# Interfaces.net
KiCad netlist of a schematic drawn in Altium Designer
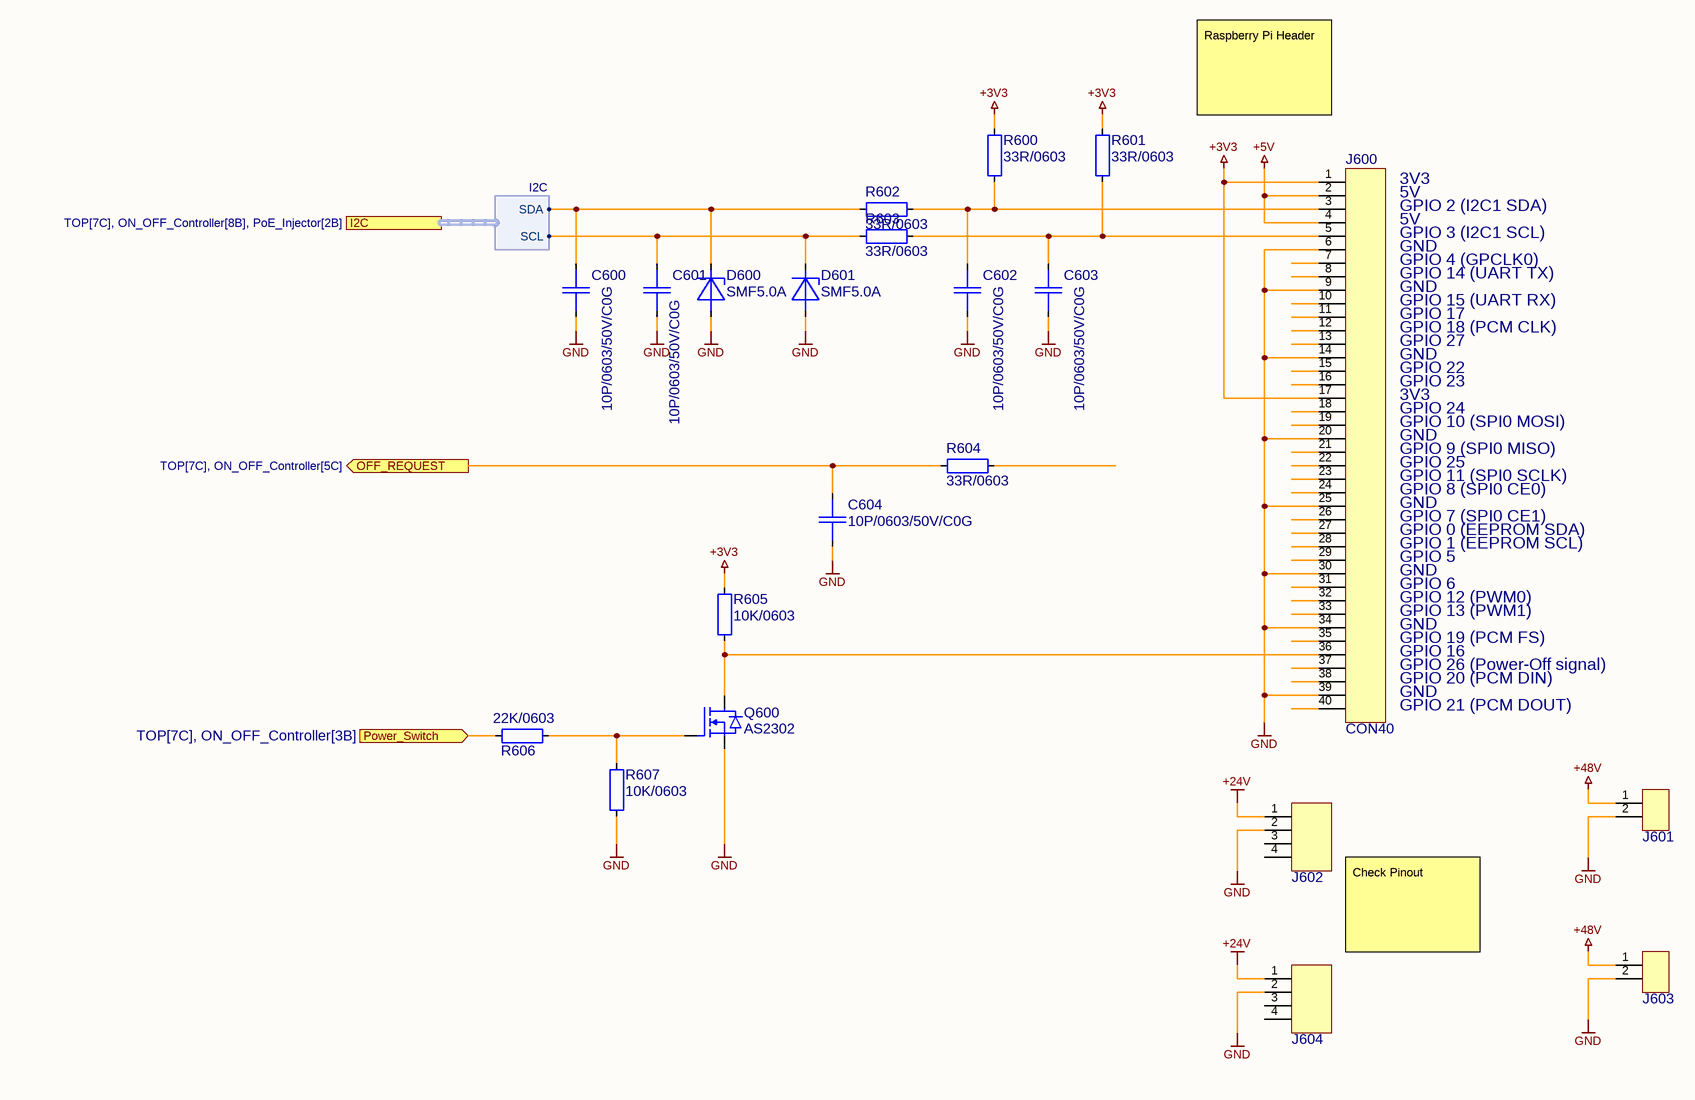
[diagram p0: Interfaces.SchDoc]

(export (version "E")
  (design (tool "Eeschema 10.0.6"))
  (components
    (comp (ref "C600")
      (value "10P/0603/50V/C0G")
      (footprint "CAP0603_C0G")
      (description "CAP SM 0603 10pF 50V C0G")
      (fields (field (name "MANUFACTURER") "GENERIC"))
      (libsource (lib "daniw_altium_lib") (part "C"))
    )
    (comp (ref "C601")
      (value "10P/0603/50V/C0G")
      (footprint "CAP0603_C0G")
      (description "CAP SM 0603 10pF 50V C0G")
      (fields (field (name "MANUFACTURER") "GENERIC"))
      (libsource (lib "daniw_altium_lib") (part "C"))
    )
    (comp (ref "C602")
      (value "10P/0603/50V/C0G")
      (footprint "CAP0603_C0G")
      (description "CAP SM 0603 10pF 50V C0G")
      (fields (field (name "MANUFACTURER") "GENERIC"))
      (libsource (lib "daniw_altium_lib") (part "C"))
    )
    (comp (ref "C603")
      (value "10P/0603/50V/C0G")
      (footprint "CAP0603_C0G")
      (description "CAP SM 0603 10pF 50V C0G")
      (fields (field (name "MANUFACTURER") "GENERIC"))
      (libsource (lib "daniw_altium_lib") (part "C"))
    )
    (comp (ref "C604")
      (value "10P/0603/50V/C0G")
      (footprint "CAP0603_C0G")
      (description "CAP SM 0603 10pF 50V C0G")
      (fields (field (name "MANUFACTURER") "GENERIC"))
      (libsource (lib "daniw_altium_lib") (part "C"))
    )
    (comp (ref "D600")
      (value "SMF5.0A")
      (footprint "SOD3720X110")
      (description "TVS DIODE 5VWM 9.2VC SOD123F")
      (fields (field (name "MANUFACTURER") "Littelfuse Inc."))
      (libsource (lib "daniw_altium_lib") (part "D_Zener"))
    )
    (comp (ref "D601")
      (value "SMF5.0A")
      (footprint "SOD3720X110")
      (description "TVS DIODE 5VWM 9.2VC SOD123F")
      (fields (field (name "MANUFACTURER") "Littelfuse Inc."))
      (libsource (lib "daniw_altium_lib") (part "D_Zener"))
    )
    (comp (ref "J600")
      (value "CON40")
      (footprint "HEAD_254_2X20")
      (description "Header 100 mil")
      (fields (field (name "PART NUMBER") "Header_2x20") (field (name "MANUFACTURER") "GENERIC"))
      (libsource (lib "daniw_altium_lib") (part "CON40"))
    )
    (comp (ref "J601")
      (value "430450212")
      (footprint "430450212")
      (fields (field (name "PART NUMBER") "Microfit_3.0_1x2_VERT_THT"))
      (libsource (lib "daniw_altium_lib") (part "CON2"))
    )
    (comp (ref "J602")
      (value "430450412")
      (footprint "430450412")
      (fields (field (name "PART NUMBER") "Microfit_3.0_2x2_VERT_THT"))
      (libsource (lib "daniw_altium_lib") (part "CON4"))
    )
    (comp (ref "J603")
      (value "430450212")
      (footprint "430450212")
      (fields (field (name "PART NUMBER") "Microfit_3.0_1x2_VERT_THT"))
      (libsource (lib "daniw_altium_lib") (part "CON2"))
    )
    (comp (ref "J604")
      (value "430450412")
      (footprint "430450412")
      (fields (field (name "PART NUMBER") "Microfit_3.0_2x2_VERT_THT"))
      (libsource (lib "daniw_altium_lib") (part "CON4"))
    )
    (comp (ref "Q600")
      (value "AS2302")
      (footprint "SOT2395P280X125-3-SE")
      (description "N-Channel 20V(D-S) MOSFET")
      (fields (field (name "MANUFACTURER") "GENERIC"))
      (libsource (lib "daniw_altium_lib") (part "MOSFET N_SOT23"))
    )
    (comp (ref "R600")
      (value "33R/0603")
      (footprint "R0603-0.40-WW")
      (description "RES SM 0603 33R")
      (fields (field (name "MANUFACTURER") "GENERIC"))
      (libsource (lib "daniw_altium_lib") (part "R"))
    )
    (comp (ref "R601")
      (value "33R/0603")
      (footprint "R0603-0.40-WW")
      (description "RES SM 0603 33R")
      (fields (field (name "MANUFACTURER") "GENERIC"))
      (libsource (lib "daniw_altium_lib") (part "R"))
    )
    (comp (ref "R602")
      (value "33R/0603")
      (footprint "R0603-0.40-WW")
      (description "RES SM 0603 33R")
      (fields (field (name "MANUFACTURER") "GENERIC"))
      (libsource (lib "daniw_altium_lib") (part "R"))
    )
    (comp (ref "R603")
      (value "33R/0603")
      (footprint "R0603-0.40-WW")
      (description "RES SM 0603 33R")
      (fields (field (name "MANUFACTURER") "GENERIC"))
      (libsource (lib "daniw_altium_lib") (part "R"))
    )
    (comp (ref "R604")
      (value "33R/0603")
      (footprint "R0603-0.40-WW")
      (description "RES SM 0603 33R")
      (fields (field (name "MANUFACTURER") "GENERIC"))
      (libsource (lib "daniw_altium_lib") (part "R"))
    )
    (comp (ref "R605")
      (value "10K/0603")
      (footprint "R0603-0.40-WW")
      (description "RES SM 0603 10K")
      (fields (field (name "MANUFACTURER") "GENERIC"))
      (libsource (lib "daniw_altium_lib") (part "R"))
    )
    (comp (ref "R606")
      (value "22K/0603")
      (footprint "R0603-0.40-WW")
      (description "RES SM 0603 22K")
      (fields (field (name "MANUFACTURER") "GENERIC"))
      (libsource (lib "daniw_altium_lib") (part "R"))
    )
    (comp (ref "R607")
      (value "10K/0603")
      (footprint "R0603-0.40-WW")
      (description "RES SM 0603 10K")
      (fields (field (name "MANUFACTURER") "GENERIC"))
      (libsource (lib "daniw_altium_lib") (part "R"))
    )
  )
  (nets
    (net (code "2") (name "+3V3") (class "Default")
      (node (ref "J600") (pin "1") (pintype "passive"))
      (node (ref "J600") (pin "17") (pintype "passive"))
      (node (ref "R600") (pin "2") (pinfunction "2_2") (pintype "passive"))
      (node (ref "R601") (pin "2") (pinfunction "2_2") (pintype "passive"))
      (node (ref "R605") (pin "1") (pinfunction "1_1") (pintype "passive"))
    )
    (net (code "3") (name "+5V") (class "Default")
      (node (ref "J600") (pin "2") (pintype "passive"))
      (node (ref "J600") (pin "4") (pintype "passive"))
    )
    (net (code "4") (name "+24V") (class "Default")
      (node (ref "J602") (pin "1") (pintype "passive"))
      (node (ref "J604") (pin "1") (pintype "passive"))
    )
    (net (code "5") (name "+48V") (class "Default")
      (node (ref "J601") (pin "1") (pintype "passive"))
      (node (ref "J603") (pin "1") (pintype "passive"))
    )
    (net (code "6") (name "/OFF_REQUEST") (class "Default")
      (node (ref "C604") (pin "1") (pinfunction "1_1") (pintype "passive"))
      (node (ref "R604") (pin "1") (pinfunction "1_1") (pintype "passive"))
    )
    (net (code "7") (name "/Power_Switch") (class "Default")
      (node (ref "R606") (pin "1") (pinfunction "1_1") (pintype "passive"))
    )
    (net (code "9") (name "GND") (class "Default")
      (node (ref "C600") (pin "2") (pinfunction "2_2") (pintype "passive"))
      (node (ref "C601") (pin "2") (pinfunction "2_2") (pintype "passive"))
      (node (ref "C602") (pin "2") (pinfunction "2_2") (pintype "passive"))
      (node (ref "C603") (pin "2") (pinfunction "2_2") (pintype "passive"))
      (node (ref "C604") (pin "2") (pinfunction "2_2") (pintype "passive"))
      (node (ref "D600") (pin "2") (pinfunction "2_2") (pintype "passive"))
      (node (ref "D601") (pin "2") (pinfunction "2_2") (pintype "passive"))
      (node (ref "J600") (pin "14") (pintype "passive"))
      (node (ref "J600") (pin "20") (pintype "passive"))
      (node (ref "J600") (pin "25") (pintype "passive"))
      (node (ref "J600") (pin "30") (pintype "passive"))
      (node (ref "J600") (pin "34") (pintype "passive"))
      (node (ref "J600") (pin "39") (pintype "passive"))
      (node (ref "J600") (pin "6") (pintype "passive"))
      (node (ref "J600") (pin "9") (pintype "passive"))
      (node (ref "J601") (pin "2") (pintype "passive"))
      (node (ref "J602") (pin "2") (pintype "passive"))
      (node (ref "J603") (pin "2") (pintype "passive"))
      (node (ref "J604") (pin "2") (pintype "passive"))
      (node (ref "Q600") (pin "2") (pinfunction "SOURCE_2") (pintype "passive"))
      (node (ref "R607") (pin "2") (pinfunction "2_2") (pintype "passive"))
    )
    (net (code "10") (name "Net-(C600-Pad1)") (class "Default")
      (node (ref "C600") (pin "1") (pinfunction "1_1") (pintype "passive"))
      (node (ref "D600") (pin "1") (pinfunction "1_1") (pintype "passive"))
      (node (ref "R602") (pin "1") (pinfunction "1_1") (pintype "passive"))
    )
    (net (code "11") (name "Net-(C601-Pad1)") (class "Default")
      (node (ref "C601") (pin "1") (pinfunction "1_1") (pintype "passive"))
      (node (ref "D601") (pin "1") (pinfunction "1_1") (pintype "passive"))
      (node (ref "R603") (pin "1") (pinfunction "1_1") (pintype "passive"))
    )
    (net (code "12") (name "Net-(C602-Pad1)") (class "Default")
      (node (ref "C602") (pin "1") (pinfunction "1_1") (pintype "passive"))
      (node (ref "J600") (pin "3") (pintype "passive"))
      (node (ref "R600") (pin "1") (pinfunction "1_1") (pintype "passive"))
      (node (ref "R602") (pin "2") (pinfunction "2_2") (pintype "passive"))
    )
    (net (code "13") (name "Net-(C603-Pad1)") (class "Default")
      (node (ref "C603") (pin "1") (pinfunction "1_1") (pintype "passive"))
      (node (ref "J600") (pin "5") (pintype "passive"))
      (node (ref "R601") (pin "1") (pinfunction "1_1") (pintype "passive"))
      (node (ref "R603") (pin "2") (pinfunction "2_2") (pintype "passive"))
    )
    (net (code "14") (name "Net-(Q600-DRAIN)") (class "Default")
      (node (ref "J600") (pin "36") (pintype "passive"))
      (node (ref "Q600") (pin "3") (pinfunction "DRAIN_3") (pintype "passive"))
      (node (ref "R605") (pin "2") (pinfunction "2_2") (pintype "passive"))
    )
    (net (code "15") (name "Net-(Q600-GATE)") (class "Default")
      (node (ref "Q600") (pin "1") (pinfunction "GATE_1") (pintype "passive"))
      (node (ref "R606") (pin "2") (pinfunction "2_2") (pintype "passive"))
      (node (ref "R607") (pin "1") (pinfunction "1_1") (pintype "passive"))
    )
    (net (code "16") (name "unconnected-(J600-Pad7)") (class "Default")
      (node (ref "J600") (pin "7") (pintype "passive"))
    )
    (net (code "17") (name "unconnected-(J600-Pad8)") (class "Default")
      (node (ref "J600") (pin "8") (pintype "passive"))
    )
    (net (code "18") (name "unconnected-(J600-Pad10)") (class "Default")
      (node (ref "J600") (pin "10") (pintype "passive"))
    )
    (net (code "19") (name "unconnected-(J600-Pad11)") (class "Default")
      (node (ref "J600") (pin "11") (pintype "passive"))
    )
    (net (code "20") (name "unconnected-(J600-Pad12)") (class "Default")
      (node (ref "J600") (pin "12") (pintype "passive"))
    )
    (net (code "21") (name "unconnected-(J600-Pad13)") (class "Default")
      (node (ref "J600") (pin "13") (pintype "passive"))
    )
    (net (code "22") (name "unconnected-(J600-Pad15)") (class "Default")
      (node (ref "J600") (pin "15") (pintype "passive"))
    )
    (net (code "23") (name "unconnected-(J600-Pad16)") (class "Default")
      (node (ref "J600") (pin "16") (pintype "passive"))
    )
    (net (code "24") (name "unconnected-(J600-Pad18)") (class "Default")
      (node (ref "J600") (pin "18") (pintype "passive"))
    )
    (net (code "25") (name "unconnected-(J600-Pad19)") (class "Default")
      (node (ref "J600") (pin "19") (pintype "passive"))
    )
    (net (code "26") (name "unconnected-(J600-Pad21)") (class "Default")
      (node (ref "J600") (pin "21") (pintype "passive"))
    )
    (net (code "27") (name "unconnected-(J600-Pad22)") (class "Default")
      (node (ref "J600") (pin "22") (pintype "passive"))
    )
    (net (code "28") (name "unconnected-(J600-Pad23)") (class "Default")
      (node (ref "J600") (pin "23") (pintype "passive"))
    )
    (net (code "29") (name "unconnected-(J600-Pad24)") (class "Default")
      (node (ref "J600") (pin "24") (pintype "passive"))
    )
    (net (code "30") (name "unconnected-(J600-Pad26)") (class "Default")
      (node (ref "J600") (pin "26") (pintype "passive"))
    )
    (net (code "31") (name "unconnected-(J600-Pad27)") (class "Default")
      (node (ref "J600") (pin "27") (pintype "passive"))
    )
    (net (code "32") (name "unconnected-(J600-Pad28)") (class "Default")
      (node (ref "J600") (pin "28") (pintype "passive"))
    )
    (net (code "33") (name "unconnected-(J600-Pad29)") (class "Default")
      (node (ref "J600") (pin "29") (pintype "passive"))
    )
    (net (code "34") (name "unconnected-(J600-Pad31)") (class "Default")
      (node (ref "J600") (pin "31") (pintype "passive"))
    )
    (net (code "35") (name "unconnected-(J600-Pad32)") (class "Default")
      (node (ref "J600") (pin "32") (pintype "passive"))
    )
    (net (code "36") (name "unconnected-(J600-Pad33)") (class "Default")
      (node (ref "J600") (pin "33") (pintype "passive"))
    )
    (net (code "37") (name "unconnected-(J600-Pad35)") (class "Default")
      (node (ref "J600") (pin "35") (pintype "passive"))
    )
    (net (code "38") (name "unconnected-(J600-Pad37)") (class "Default")
      (node (ref "J600") (pin "37") (pintype "passive"))
    )
    (net (code "39") (name "unconnected-(J600-Pad38)") (class "Default")
      (node (ref "J600") (pin "38") (pintype "passive"))
    )
    (net (code "40") (name "unconnected-(J600-Pad40)") (class "Default")
      (node (ref "J600") (pin "40") (pintype "passive"))
    )
    (net (code "41") (name "unconnected-(J602-Pad3)") (class "Default")
      (node (ref "J602") (pin "3") (pintype "passive"))
    )
    (net (code "42") (name "unconnected-(J602-Pad4)") (class "Default")
      (node (ref "J602") (pin "4") (pintype "passive"))
    )
    (net (code "43") (name "unconnected-(J604-Pad3)") (class "Default")
      (node (ref "J604") (pin "3") (pintype "passive"))
    )
    (net (code "44") (name "unconnected-(J604-Pad4)") (class "Default")
      (node (ref "J604") (pin "4") (pintype "passive"))
    )
    (net (code "45") (name "unconnected-(R604-Pad2)") (class "Default")
      (node (ref "R604") (pin "2") (pinfunction "2_2") (pintype "passive"))
    )
  )
)
